# multitask_attiny85_no_icsp.net
KiCad netlist of a schematic drawn in EAGLE
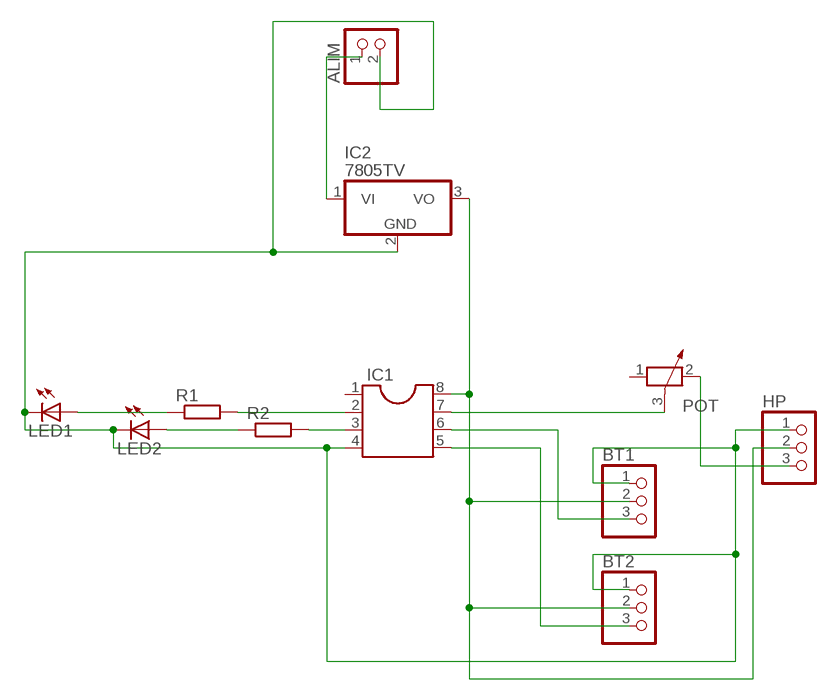
[diagram p0: schematic, sheet 1]

(export (version "E")
  (design (tool "Eeschema 10.0.6"))
  (components
    (comp (ref "ALIM")
      (value "PINHD-1X2")
      (footprint "eagle-import:1X02")
      (libsource (lib "eagle-import") (part "PINHD-1X2"))
    )
    (comp (ref "BT1")
      (value "PINHD-1X3")
      (footprint "eagle-import:1X03")
      (libsource (lib "eagle-import") (part "PINHD-1X3"))
    )
    (comp (ref "BT2")
      (value "PINHD-1X3")
      (footprint "eagle-import:1X03")
      (libsource (lib "eagle-import") (part "PINHD-1X3"))
    )
    (comp (ref "HP")
      (value "PINHD-1X3")
      (footprint "eagle-import:1X03")
      (libsource (lib "eagle-import") (part "PINHD-1X3"))
    )
    (comp (ref "IC1")
      (value "DIL8S")
      (footprint "eagle-import:SOCKET-08")
      (libsource (lib "eagle-import") (part "DIL8S"))
    )
    (comp (ref "IC2")
      (value "7805TV")
      (footprint "eagle-import:TO220V")
      (libsource (lib "eagle-import") (part "78TV05"))
    )
    (comp (ref "LED1")
      (value "LED5MM")
      (footprint "eagle-import:LED5MM")
      (libsource (lib "eagle-import") (part "LED5MM"))
    )
    (comp (ref "LED2")
      (value "LED5MM")
      (footprint "eagle-import:LED5MM")
      (libsource (lib "eagle-import") (part "LED5MM"))
    )
    (comp (ref "POT")
      (value "POTENTIOMETER_PT-10")
      (footprint "eagle-import:PT-10")
      (libsource (lib "eagle-import") (part "POTENTIOMETER_PT-10"))
    )
    (comp (ref "R1")
      (value "R-EU_0204/7")
      (footprint "eagle-import:0204_7")
      (libsource (lib "eagle-import") (part "R-EU_0204/7"))
    )
    (comp (ref "R2")
      (value "R-EU_0204/7")
      (footprint "eagle-import:0204_7")
      (libsource (lib "eagle-import") (part "R-EU_0204/7"))
    )
  )
  (nets
    (net (code "1") (name "Net-(BT1-Pad3)") (class "Default")
      (node (ref "BT1") (pin "3") (pinfunction "3_3") (pintype "passive"))
      (node (ref "IC1") (pin "6") (pinfunction "6_6") (pintype "passive"))
    )
    (net (code "2") (name "Net-(BT2-Pad3)") (class "Default")
      (node (ref "BT2") (pin "3") (pinfunction "3_3") (pintype "passive"))
      (node (ref "IC1") (pin "5") (pinfunction "5_5") (pintype "passive"))
    )
    (net (code "3") (name "Net-(HP-Pad3)") (class "Default")
      (node (ref "HP") (pin "3") (pinfunction "3_3") (pintype "passive"))
      (node (ref "POT") (pin "2") (pinfunction "2_2") (pintype "passive"))
    )
    (net (code "4") (name "Net-(IC1-Pad2)") (class "Default")
      (node (ref "IC1") (pin "2") (pinfunction "2_2") (pintype "passive"))
      (node (ref "R1") (pin "2") (pinfunction "2_2") (pintype "passive"))
    )
    (net (code "5") (name "Net-(IC1-Pad3)") (class "Default")
      (node (ref "IC1") (pin "3") (pinfunction "3_3") (pintype "passive"))
      (node (ref "R2") (pin "2") (pinfunction "2_2") (pintype "passive"))
    )
    (net (code "6") (name "Net-(IC1-Pad7)") (class "Default")
      (node (ref "IC1") (pin "7") (pinfunction "7_7") (pintype "passive"))
      (node (ref "POT") (pin "3") (pinfunction "3_3") (pintype "passive"))
    )
    (net (code "7") (name "Net-(IC2-GND)") (class "Default")
      (node (ref "ALIM") (pin "2") (pinfunction "2_2") (pintype "passive"))
      (node (ref "BT1") (pin "1") (pinfunction "1_1") (pintype "passive"))
      (node (ref "BT2") (pin "1") (pinfunction "1_1") (pintype "passive"))
      (node (ref "HP") (pin "1") (pinfunction "1_1") (pintype "passive"))
      (node (ref "IC1") (pin "4") (pinfunction "4_4") (pintype "passive"))
      (node (ref "IC2") (pin "2") (pinfunction "GND_2") (pintype "passive"))
      (node (ref "LED1") (pin "K") (pinfunction "C_K") (pintype "passive"))
      (node (ref "LED2") (pin "K") (pinfunction "C_K") (pintype "passive"))
    )
    (net (code "8") (name "Net-(IC2-VI)") (class "Default")
      (node (ref "ALIM") (pin "1") (pinfunction "1_1") (pintype "passive"))
      (node (ref "IC2") (pin "1") (pinfunction "VI_1") (pintype "input"))
    )
    (net (code "9") (name "Net-(IC2-VO)") (class "Default")
      (node (ref "BT1") (pin "2") (pinfunction "2_2") (pintype "passive"))
      (node (ref "BT2") (pin "2") (pinfunction "2_2") (pintype "passive"))
      (node (ref "HP") (pin "2") (pinfunction "2_2") (pintype "passive"))
      (node (ref "IC1") (pin "8") (pinfunction "8_8") (pintype "passive"))
      (node (ref "IC2") (pin "3") (pinfunction "VO_3") (pintype "passive"))
    )
    (net (code "10") (name "Net-(LED1-PadA)") (class "Default")
      (node (ref "LED1") (pin "A") (pinfunction "A_A") (pintype "passive"))
      (node (ref "R1") (pin "1") (pinfunction "1_1") (pintype "passive"))
    )
    (net (code "11") (name "Net-(LED2-PadA)") (class "Default")
      (node (ref "LED2") (pin "A") (pinfunction "A_A") (pintype "passive"))
      (node (ref "R2") (pin "1") (pinfunction "1_1") (pintype "passive"))
    )
    (net (code "12") (name "unconnected-(IC1-Pad1)") (class "Default")
      (node (ref "IC1") (pin "1") (pinfunction "1_1") (pintype "passive"))
    )
    (net (code "13") (name "unconnected-(POT-Pad1)") (class "Default")
      (node (ref "POT") (pin "1") (pinfunction "1_1") (pintype "passive"))
    )
  )
)
